# CurrentSensor.net
KiCad netlist of a schematic drawn in Altium Designer
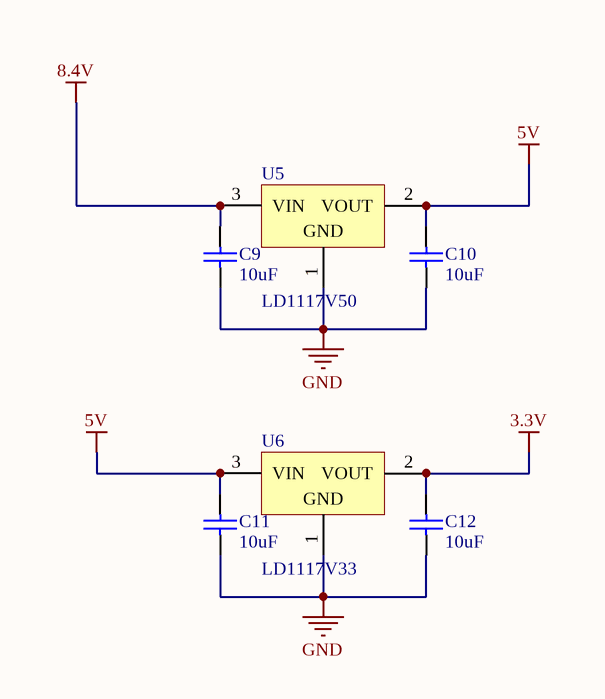
[diagram p0: CurrentSensor.SchDoc]

(export (version "E")
  (design (tool "Eeschema 10.0.6"))
  (components
    (comp (ref "C9")
      (value "10uF")
      (footprint "CAPC2013X145X48ML20T23")
      (fields (field (name "PART NUMBER") "VJ0805Y103KXBBC31") (field (name "MANUFACTURER") "Vitramon"))
      (libsource (lib "Altium Content Vault") (part "CAP"))
    )
    (comp (ref "C10")
      (value "10uF")
      (footprint "CAPC2013X145X48ML20T23")
      (fields (field (name "PART NUMBER") "VJ0805Y103KXBBC31") (field (name "MANUFACTURER") "Vitramon"))
      (libsource (lib "Altium Content Vault") (part "CAP"))
    )
    (comp (ref "C11")
      (value "10uF")
      (footprint "CAPC2013X145X48ML20T23")
      (fields (field (name "PART NUMBER") "VJ0805Y103KXBBC31") (field (name "MANUFACTURER") "Vitramon"))
      (libsource (lib "Altium Content Vault") (part "CAP"))
    )
    (comp (ref "C12")
      (value "10uF")
      (footprint "CAPC2013X145X48ML20T23")
      (fields (field (name "PART NUMBER") "VJ0805Y103KXBBC31") (field (name "MANUFACTURER") "Vitramon"))
      (libsource (lib "Altium Content Vault") (part "CAP"))
    )
    (comp (ref "U5")
      (value "LD1117V50")
      (footprint "TO220")
      (description "Fixed Low Drop Positive Voltage Regulator, 5V, 3-Pin TO-220")
      (libsource (lib "Altium Content Vault") (part "PM-REG-LD1117V-SIL3"))
    )
    (comp (ref "U6")
      (value "LD1117V33")
      (footprint "TO220")
      (description "Fixed Low Drop Positive Voltage Regulator, 3.3V, 3-Pin TO-220")
      (libsource (lib "Altium Content Vault") (part "PM-REG-LD1117V-SIL3"))
    )
  )
  (nets
    (net (code "1") (name "3.3V") (class "Default")
      (node (ref "C12") (pin "1") (pinfunction "1_1") (pintype "passive"))
      (node (ref "U6") (pin "2") (pinfunction "VOUT_2") (pintype "power_in"))
    )
    (net (code "2") (name "5V") (class "Default")
      (node (ref "C10") (pin "1") (pinfunction "1_1") (pintype "passive"))
      (node (ref "C11") (pin "1") (pinfunction "1_1") (pintype "passive"))
      (node (ref "U5") (pin "2") (pinfunction "VOUT_2") (pintype "power_in"))
      (node (ref "U6") (pin "3") (pinfunction "VIN_3") (pintype "power_in"))
    )
    (net (code "3") (name "8.4V") (class "Default")
      (node (ref "C9") (pin "1") (pinfunction "1_1") (pintype "passive"))
      (node (ref "U5") (pin "3") (pinfunction "VIN_3") (pintype "power_in"))
    )
    (net (code "4") (name "GND") (class "Default")
      (node (ref "C10") (pin "2") (pinfunction "2_2") (pintype "passive"))
      (node (ref "C11") (pin "2") (pinfunction "2_2") (pintype "passive"))
      (node (ref "C12") (pin "2") (pinfunction "2_2") (pintype "passive"))
      (node (ref "C9") (pin "2") (pinfunction "2_2") (pintype "passive"))
      (node (ref "U5") (pin "1") (pinfunction "GND_1") (pintype "power_in"))
      (node (ref "U6") (pin "1") (pinfunction "GND_1") (pintype "power_in"))
    )
  )
)
